# SparkFun_XBee_Serial_Explorer.net
KiCad netlist of a schematic drawn in EAGLE
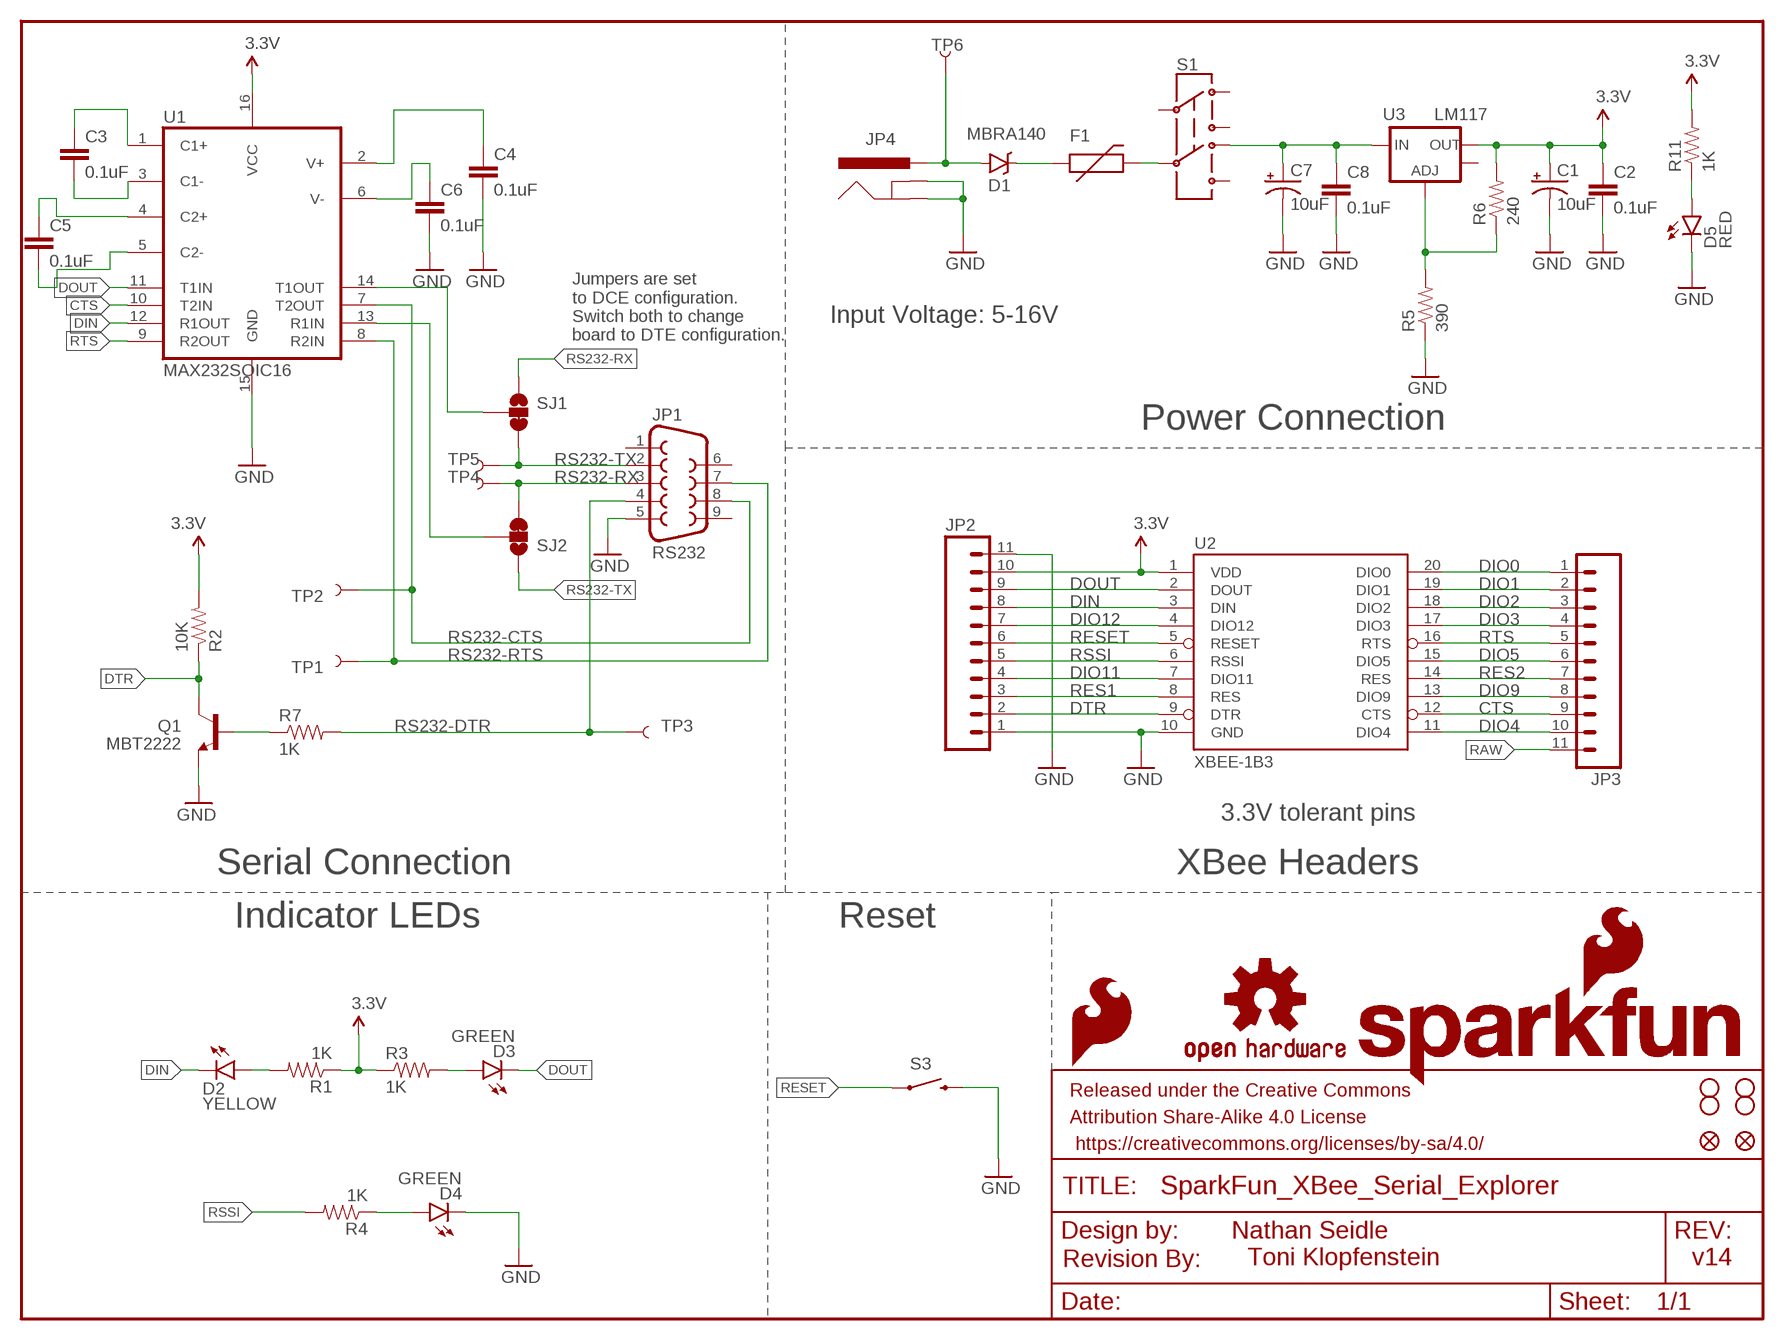
[diagram p0: schematic, sheet 1]

(export (version "E")
  (design (tool "Eeschema 10.0.6"))
  (components
    (comp (ref "C1")
      (value "10uF")
      (footprint "eagle-import:EIA3216")
      (libsource (lib "eagle-import") (part "10UF-16V-10%(TANT)"))
    )
    (comp (ref "C2")
      (value "0.1uF")
      (footprint "eagle-import:0603-CAP")
      (libsource (lib "eagle-import") (part "0.1UF-25V(+80/-20%)(0603)"))
    )
    (comp (ref "C3")
      (value "0.1uF")
      (footprint "eagle-import:0603-CAP")
      (libsource (lib "eagle-import") (part "0.1UF-25V(+80/-20%)(0603)"))
    )
    (comp (ref "C4")
      (value "0.1uF")
      (footprint "eagle-import:0603-CAP")
      (libsource (lib "eagle-import") (part "0.1UF-25V(+80/-20%)(0603)"))
    )
    (comp (ref "C5")
      (value "0.1uF")
      (footprint "eagle-import:0603-CAP")
      (libsource (lib "eagle-import") (part "0.1UF-25V(+80/-20%)(0603)"))
    )
    (comp (ref "C6")
      (value "0.1uF")
      (footprint "eagle-import:0603-CAP")
      (libsource (lib "eagle-import") (part "0.1UF-25V(+80/-20%)(0603)"))
    )
    (comp (ref "C7")
      (value "10uF")
      (footprint "eagle-import:EIA3216")
      (libsource (lib "eagle-import") (part "10UF-16V-10%(TANT)"))
    )
    (comp (ref "C8")
      (value "0.1uF")
      (footprint "eagle-import:0603-CAP")
      (libsource (lib "eagle-import") (part "0.1UF-25V(+80/-20%)(0603)"))
    )
    (comp (ref "D1")
      (value "MBRA140")
      (footprint "eagle-import:SMA-DIODE")
      (libsource (lib "eagle-import") (part "DIODE-SCHOTTKY-MBRA140"))
    )
    (comp (ref "D2")
      (value "YELLOW")
      (footprint "eagle-import:LED-1206")
      (libsource (lib "eagle-import") (part "LED-YELLOWLARGE"))
    )
    (comp (ref "D3")
      (value "GREEN")
      (footprint "eagle-import:LED-1206")
      (libsource (lib "eagle-import") (part "LED-GREENLARGE"))
    )
    (comp (ref "D4")
      (value "GREEN")
      (footprint "eagle-import:LED-1206")
      (libsource (lib "eagle-import") (part "LED-GREENLARGE"))
    )
    (comp (ref "D5")
      (value "RED")
      (footprint "eagle-import:LED-1206")
      (libsource (lib "eagle-import") (part "LED-RED1206"))
    )
    (comp (ref "F1")
      (value "PTCTHERMISTOR1206")
      (footprint "eagle-import:PTC-1206")
      (libsource (lib "eagle-import") (part "PTCTHERMISTOR1206"))
    )
    (comp (ref "FRAME1")
      (value "FRAME-LETTER")
      (footprint "eagle-import:CREATIVE_COMMONS")
      (libsource (lib "eagle-import") (part "FRAME-LETTER"))
    )
    (comp (ref "JP1")
      (value "RS232")
      (footprint "eagle-import:DB9")
      (libsource (lib "eagle-import") (part "DB9FEMALE"))
    )
    (comp (ref "JP2")
      (value "M11PTH")
      (footprint "eagle-import:1X11")
      (libsource (lib "eagle-import") (part "M11PTH"))
    )
    (comp (ref "JP3")
      (value "M11PTH")
      (footprint "eagle-import:1X11")
      (libsource (lib "eagle-import") (part "M11PTH"))
    )
    (comp (ref "JP4")
      (value "POWER_JACKPTH_LOCK")
      (footprint "eagle-import:POWER_JACK_PTH_LOCK")
      (libsource (lib "eagle-import") (part "POWER_JACKPTH_LOCK"))
    )
    (comp (ref "LOGO1")
      (value "OSHW-LOGOL")
      (footprint "eagle-import:OSHW-LOGO-L")
      (libsource (lib "eagle-import") (part "OSHW-LOGOL"))
    )
    (comp (ref "LOGO2")
      (value "SFE_LOGO_NAME_FLAME.2_INCH")
      (footprint "eagle-import:SFE_LOGO_NAME_FLAME_.2")
      (libsource (lib "eagle-import") (part "SFE_LOGO_NAME_FLAME.2_INCH"))
    )
    (comp (ref "LOGO3")
      (value "SFE_LOGO_FLAME.1_INCH")
      (footprint "eagle-import:SFE_LOGO_FLAME_.1")
      (libsource (lib "eagle-import") (part "SFE_LOGO_FLAME.1_INCH"))
    )
    (comp (ref "Q1")
      (value "MBT2222")
      (footprint "eagle-import:SOT23-3")
      (libsource (lib "eagle-import") (part "TRANSISTOR_NPNSOT23-3"))
    )
    (comp (ref "R1")
      (value "1K")
      (footprint "eagle-import:0603-RES")
      (libsource (lib "eagle-import") (part "1KOHM-1/10W-1%(0603)"))
    )
    (comp (ref "R2")
      (value "10K")
      (footprint "eagle-import:0603-RES")
      (libsource (lib "eagle-import") (part "10KOHM-1/10W-1%(0603)0603"))
    )
    (comp (ref "R3")
      (value "1K")
      (footprint "eagle-import:0603-RES")
      (libsource (lib "eagle-import") (part "1KOHM-1/10W-1%(0603)"))
    )
    (comp (ref "R4")
      (value "1K")
      (footprint "eagle-import:0603-RES")
      (libsource (lib "eagle-import") (part "1KOHM-1/10W-1%(0603)"))
    )
    (comp (ref "R5")
      (value "390")
      (footprint "eagle-import:0603-RES")
      (libsource (lib "eagle-import") (part "390OHM1/10W1%(0603)"))
    )
    (comp (ref "R6")
      (value "240")
      (footprint "eagle-import:0603-RES")
      (libsource (lib "eagle-import") (part "240OHM1/10W1%(0603)"))
    )
    (comp (ref "R7")
      (value "1K")
      (footprint "eagle-import:0603-RES")
      (libsource (lib "eagle-import") (part "1KOHM-1/10W-1%(0603)"))
    )
    (comp (ref "R11")
      (value "1K")
      (footprint "eagle-import:0603-RES")
      (libsource (lib "eagle-import") (part "1KOHM-1/10W-1%(0603)"))
    )
    (comp (ref "S1")
      (value "AYZ0202")
      (footprint "eagle-import:AYZ0202")
      (libsource (lib "eagle-import") (part "AYZ0202"))
    )
    (comp (ref "S3")
      (value "TAC_SWITCHSMD")
      (footprint "eagle-import:TACTILE-SWITCH-SMD")
      (libsource (lib "eagle-import") (part "SWITCH-MOMENTARY-2SMD-REDUNDANT"))
    )
    (comp (ref "SJ1")
      (value "JUMPER-PAD-3-2OF3_NC_BY_TRACE_SMALL")
      (footprint "eagle-import:PAD-JUMPER-3-2OF3_NC_BY_TRACE_YES_SILK_FULL_BOX")
      (libsource (lib "eagle-import") (part "JUMPER-PAD-3-2OF3_NC_BY_TRACE_SMALL"))
    )
    (comp (ref "SJ2")
      (value "JUMPER-PAD-3-2OF3_NC_BY_TRACE_SMALL")
      (footprint "eagle-import:PAD-JUMPER-3-2OF3_NC_BY_TRACE_YES_SILK_FULL_BOX")
      (libsource (lib "eagle-import") (part "JUMPER-PAD-3-2OF3_NC_BY_TRACE_SMALL"))
    )
    (comp (ref "TP1")
      (value "TEST-POINTTP_15TH_THRU")
      (footprint "eagle-import:TP_15TH")
      (libsource (lib "eagle-import") (part "TEST-POINTTP_15TH_THRU"))
    )
    (comp (ref "TP2")
      (value "TEST-POINTTP_15TH_THRU")
      (footprint "eagle-import:TP_15TH")
      (libsource (lib "eagle-import") (part "TEST-POINTTP_15TH_THRU"))
    )
    (comp (ref "TP3")
      (value "TEST-POINTTP_15TH_THRU")
      (footprint "eagle-import:TP_15TH")
      (libsource (lib "eagle-import") (part "TEST-POINTTP_15TH_THRU"))
    )
    (comp (ref "TP4")
      (value "TEST-POINTTP_15TH_THRU")
      (footprint "eagle-import:TP_15TH")
      (libsource (lib "eagle-import") (part "TEST-POINTTP_15TH_THRU"))
    )
    (comp (ref "TP5")
      (value "TEST-POINTTP_15TH_THRU")
      (footprint "eagle-import:TP_15TH")
      (libsource (lib "eagle-import") (part "TEST-POINTTP_15TH_THRU"))
    )
    (comp (ref "TP6")
      (value "TEST-POINTTP_15TH_THRU")
      (footprint "eagle-import:TP_15TH")
      (libsource (lib "eagle-import") (part "TEST-POINTTP_15TH_THRU"))
    )
    (comp (ref "U$1")
      (value "REVISION")
      (footprint "eagle-import:REVISION")
      (libsource (lib "eagle-import") (part "REVISION"))
    )
    (comp (ref "U$5")
      (value "STAND-OFF")
      (footprint "eagle-import:STAND-OFF")
      (libsource (lib "eagle-import") (part "STAND-OFF"))
    )
    (comp (ref "U$7")
      (value "FIDUCIAL1X2")
      (footprint "eagle-import:FIDUCIAL-1X2")
      (libsource (lib "eagle-import") (part "FIDUCIAL1X2"))
    )
    (comp (ref "U$9")
      (value "STAND-OFF")
      (footprint "eagle-import:STAND-OFF")
      (libsource (lib "eagle-import") (part "STAND-OFF"))
    )
    (comp (ref "U$10")
      (value "STAND-OFF")
      (footprint "eagle-import:STAND-OFF")
      (libsource (lib "eagle-import") (part "STAND-OFF"))
    )
    (comp (ref "U$11")
      (value "STAND-OFF")
      (footprint "eagle-import:STAND-OFF")
      (libsource (lib "eagle-import") (part "STAND-OFF"))
    )
    (comp (ref "U$16")
      (value "FIDUCIAL1X2")
      (footprint "eagle-import:FIDUCIAL-1X2")
      (libsource (lib "eagle-import") (part "FIDUCIAL1X2"))
    )
    (comp (ref "U1")
      (value "MAX232SOIC16")
      (footprint "eagle-import:SO016")
      (libsource (lib "eagle-import") (part "MAX232SOIC16"))
    )
    (comp (ref "U2")
      (value "XBEE-1B3")
      (footprint "eagle-import:XBEE-SMD")
      (libsource (lib "eagle-import") (part "XBEE-1B3"))
    )
    (comp (ref "U3")
      (value "LM117")
      (footprint "eagle-import:SOT223")
      (libsource (lib "eagle-import") (part "V_REG_LM1117SOT223"))
    )
  )
  (nets
    (net (code "1") (name "/DIO0") (class "Default")
      (node (ref "JP3") (pin "1") (pinfunction "1_1") (pintype "passive"))
      (node (ref "U2") (pin "20") (pinfunction "DIO0_20") (pintype "bidirectional"))
    )
    (net (code "2") (name "/DIO1") (class "Default")
      (node (ref "JP3") (pin "2") (pinfunction "2_2") (pintype "passive"))
      (node (ref "U2") (pin "19") (pinfunction "DIO1_19") (pintype "bidirectional"))
    )
    (net (code "3") (name "/DIO2") (class "Default")
      (node (ref "JP3") (pin "3") (pinfunction "3_3") (pintype "passive"))
      (node (ref "U2") (pin "18") (pinfunction "DIO2_18") (pintype "bidirectional"))
    )
    (net (code "4") (name "/DIO3") (class "Default")
      (node (ref "JP3") (pin "4") (pinfunction "4_4") (pintype "passive"))
      (node (ref "U2") (pin "17") (pinfunction "DIO3_17") (pintype "bidirectional"))
    )
    (net (code "5") (name "/DIO4") (class "Default")
      (node (ref "JP3") (pin "10") (pinfunction "10_10") (pintype "passive"))
      (node (ref "U2") (pin "11") (pinfunction "DIO4_11") (pintype "bidirectional"))
    )
    (net (code "6") (name "/DIO5") (class "Default")
      (node (ref "JP3") (pin "6") (pinfunction "6_6") (pintype "passive"))
      (node (ref "U2") (pin "15") (pinfunction "DIO5_15") (pintype "bidirectional"))
    )
    (net (code "7") (name "/DIO9") (class "Default")
      (node (ref "JP3") (pin "8") (pinfunction "8_8") (pintype "passive"))
      (node (ref "U2") (pin "13") (pinfunction "DIO9_13") (pintype "bidirectional"))
    )
    (net (code "8") (name "/DIO11") (class "Default")
      (node (ref "JP2") (pin "4") (pinfunction "4_4") (pintype "passive"))
      (node (ref "U2") (pin "7") (pinfunction "DIO11_7") (pintype "bidirectional"))
    )
    (net (code "9") (name "/DIO12") (class "Default")
      (node (ref "JP2") (pin "7") (pinfunction "7_7") (pintype "passive"))
      (node (ref "U2") (pin "4") (pinfunction "DIO12_4") (pintype "bidirectional"))
    )
    (net (code "10") (name "/RES1") (class "Default")
      (node (ref "JP2") (pin "3") (pinfunction "3_3") (pintype "passive"))
      (node (ref "U2") (pin "8") (pinfunction "RES_8") (pintype "bidirectional"))
    )
    (net (code "11") (name "/RES2") (class "Default")
      (node (ref "JP3") (pin "7") (pinfunction "7_7") (pintype "passive"))
      (node (ref "U2") (pin "14") (pinfunction "RES_14") (pintype "bidirectional"))
    )
    (net (code "12") (name "/RS232-CTS") (class "Default")
      (node (ref "JP1") (pin "8") (pinfunction "8_8") (pintype "passive"))
      (node (ref "TP2") (pin "P$1") (pinfunction "1_P$1") (pintype "bidirectional"))
      (node (ref "U1") (pin "7") (pinfunction "T2OUT_7") (pintype "output"))
    )
    (net (code "13") (name "/RS232-DTR") (class "Default")
      (node (ref "JP1") (pin "4") (pinfunction "4_4") (pintype "passive"))
      (node (ref "R7") (pin "2") (pinfunction "2_2") (pintype "passive"))
      (node (ref "TP3") (pin "P$1") (pinfunction "1_P$1") (pintype "bidirectional"))
    )
    (net (code "14") (name "/RS232-RTS") (class "Default")
      (node (ref "JP1") (pin "7") (pinfunction "7_7") (pintype "passive"))
      (node (ref "TP1") (pin "P$1") (pinfunction "1_P$1") (pintype "bidirectional"))
      (node (ref "U1") (pin "8") (pinfunction "R2IN_8") (pintype "input"))
    )
    (net (code "15") (name "3.3V") (class "Default")
      (node (ref "C1") (pin "A") (pinfunction "+_A") (pintype "passive"))
      (node (ref "C2") (pin "1") (pinfunction "1_1") (pintype "passive"))
      (node (ref "JP2") (pin "10") (pinfunction "10_10") (pintype "passive"))
      (node (ref "R1") (pin "1") (pinfunction "1_1") (pintype "passive"))
      (node (ref "R11") (pin "2") (pinfunction "2_2") (pintype "passive"))
      (node (ref "R2") (pin "2") (pinfunction "2_2") (pintype "passive"))
      (node (ref "R3") (pin "1") (pinfunction "1_1") (pintype "passive"))
      (node (ref "R6") (pin "2") (pinfunction "2_2") (pintype "passive"))
      (node (ref "U1") (pin "16") (pinfunction "VCC_16") (pintype "bidirectional"))
      (node (ref "U2") (pin "1") (pinfunction "VDD_1") (pintype "power_in"))
      (node (ref "U3") (pin "2") (pinfunction "OUT_2") (pintype "output"))
    )
    (net (code "16") (name "CTS") (class "Default")
      (node (ref "JP3") (pin "9") (pinfunction "9_9") (pintype "passive"))
      (node (ref "U1") (pin "10") (pinfunction "T2IN_10") (pintype "input"))
      (node (ref "U2") (pin "12") (pinfunction "CTS_12") (pintype "output"))
    )
    (net (code "17") (name "DIN") (class "Default")
      (node (ref "D2") (pin "C") (pinfunction "C_C") (pintype "passive"))
      (node (ref "JP2") (pin "8") (pinfunction "8_8") (pintype "passive"))
      (node (ref "U1") (pin "12") (pinfunction "R1OUT_12") (pintype "output"))
      (node (ref "U2") (pin "3") (pinfunction "DIN_3") (pintype "input"))
    )
    (net (code "18") (name "DOUT") (class "Default")
      (node (ref "D3") (pin "C") (pinfunction "C_C") (pintype "passive"))
      (node (ref "JP2") (pin "9") (pinfunction "9_9") (pintype "passive"))
      (node (ref "U1") (pin "11") (pinfunction "T1IN_11") (pintype "input"))
      (node (ref "U2") (pin "2") (pinfunction "DOUT_2") (pintype "output"))
    )
    (net (code "19") (name "DTR") (class "Default")
      (node (ref "JP2") (pin "2") (pinfunction "2_2") (pintype "passive"))
      (node (ref "Q1") (pin "3") (pinfunction "C_3") (pintype "passive"))
      (node (ref "R2") (pin "1") (pinfunction "1_1") (pintype "passive"))
      (node (ref "U2") (pin "9") (pinfunction "DTR_9") (pintype "bidirectional"))
    )
    (net (code "20") (name "GND") (class "Default")
      (node (ref "C1") (pin "C") (pinfunction "-_C") (pintype "passive"))
      (node (ref "C2") (pin "2") (pinfunction "2_2") (pintype "passive"))
      (node (ref "C4") (pin "2") (pinfunction "2_2") (pintype "passive"))
      (node (ref "C6") (pin "2") (pinfunction "2_2") (pintype "passive"))
      (node (ref "C7") (pin "C") (pinfunction "-_C") (pintype "passive"))
      (node (ref "C8") (pin "2") (pinfunction "2_2") (pintype "passive"))
      (node (ref "D4") (pin "C") (pinfunction "C_C") (pintype "passive"))
      (node (ref "D5") (pin "C") (pinfunction "C_C") (pintype "passive"))
      (node (ref "JP1") (pin "5") (pinfunction "5_5") (pintype "passive"))
      (node (ref "JP2") (pin "1") (pinfunction "1_1") (pintype "passive"))
      (node (ref "JP2") (pin "11") (pinfunction "11_11") (pintype "passive"))
      (node (ref "JP4") (pin "GND") (pinfunction "GND_GND") (pintype "bidirectional"))
      (node (ref "JP4") (pin "GNDBREAK") (pinfunction "GNDBREAK_GNDBREAK") (pintype "bidirectional"))
      (node (ref "Q1") (pin "2") (pinfunction "E_2") (pintype "passive"))
      (node (ref "R5") (pin "1") (pinfunction "1_1") (pintype "passive"))
      (node (ref "S3") (pin "3") (pinfunction "2_3") (pintype "passive"))
      (node (ref "S3") (pin "4") (pinfunction "2_4") (pintype "passive"))
      (node (ref "U1") (pin "15") (pinfunction "GND_15") (pintype "bidirectional"))
      (node (ref "U2") (pin "10") (pinfunction "GND_10") (pintype "power_in"))
    )
    (net (code "21") (name "Net-(D1-PadC)") (class "Default")
      (node (ref "D1") (pin "C") (pinfunction "C_C") (pintype "passive"))
      (node (ref "F1") (pin "1") (pinfunction "1_1") (pintype "bidirectional"))
    )
    (net (code "22") (name "Net-(D2-PadA)") (class "Default")
      (node (ref "D2") (pin "A") (pinfunction "A_A") (pintype "passive"))
      (node (ref "R1") (pin "2") (pinfunction "2_2") (pintype "passive"))
    )
    (net (code "23") (name "Net-(D3-PadA)") (class "Default")
      (node (ref "D3") (pin "A") (pinfunction "A_A") (pintype "passive"))
      (node (ref "R3") (pin "2") (pinfunction "2_2") (pintype "passive"))
    )
    (net (code "24") (name "Net-(D4-PadA)") (class "Default")
      (node (ref "D4") (pin "A") (pinfunction "A_A") (pintype "passive"))
      (node (ref "R4") (pin "1") (pinfunction "1_1") (pintype "passive"))
    )
    (net (code "25") (name "Net-(D5-PadA)") (class "Default")
      (node (ref "D5") (pin "A") (pinfunction "A_A") (pintype "passive"))
      (node (ref "R11") (pin "1") (pinfunction "1_1") (pintype "passive"))
    )
    (net (code "26") (name "Net-(F1-Pad2)") (class "Default")
      (node (ref "F1") (pin "2") (pinfunction "2_2") (pintype "bidirectional"))
      (node (ref "S1") (pin "5") (pinfunction "5_5") (pintype "bidirectional"))
    )
    (net (code "27") (name "Net-(Q1-B)") (class "Default")
      (node (ref "Q1") (pin "1") (pinfunction "B_1") (pintype "passive"))
      (node (ref "R7") (pin "1") (pinfunction "1_1") (pintype "passive"))
    )
    (net (code "28") (name "Net-(TP6-1)") (class "Default")
      (node (ref "D1") (pin "A") (pinfunction "A_A") (pintype "passive"))
      (node (ref "JP4") (pin "PWR") (pinfunction "PWR_PWR") (pintype "bidirectional"))
      (node (ref "TP6") (pin "P$1") (pinfunction "1_P$1") (pintype "bidirectional"))
    )
    (net (code "29") (name "Net-(U1-C1+)") (class "Default")
      (node (ref "C3") (pin "1") (pinfunction "1_1") (pintype "passive"))
      (node (ref "U1") (pin "1") (pinfunction "C1+_1") (pintype "bidirectional"))
    )
    (net (code "30") (name "Net-(U1-C1-)") (class "Default")
      (node (ref "C3") (pin "2") (pinfunction "2_2") (pintype "passive"))
      (node (ref "U1") (pin "3") (pinfunction "C1-_3") (pintype "bidirectional"))
    )
    (net (code "31") (name "Net-(U1-C2+)") (class "Default")
      (node (ref "C5") (pin "1") (pinfunction "1_1") (pintype "passive"))
      (node (ref "U1") (pin "4") (pinfunction "C2+_4") (pintype "bidirectional"))
    )
    (net (code "32") (name "Net-(U1-C2-)") (class "Default")
      (node (ref "C5") (pin "2") (pinfunction "2_2") (pintype "passive"))
      (node (ref "U1") (pin "5") (pinfunction "C2-_5") (pintype "bidirectional"))
    )
    (net (code "33") (name "Net-(U1-R1IN)") (class "Default")
      (node (ref "SJ2") (pin "2") (pinfunction "2_2") (pintype "passive"))
      (node (ref "U1") (pin "13") (pinfunction "R1IN_13") (pintype "input"))
    )
    (net (code "34") (name "Net-(U1-T1OUT)") (class "Default")
      (node (ref "SJ1") (pin "2") (pinfunction "2_2") (pintype "passive"))
      (node (ref "U1") (pin "14") (pinfunction "T1OUT_14") (pintype "output"))
    )
    (net (code "35") (name "Net-(U1-V+)") (class "Default")
      (node (ref "C4") (pin "1") (pinfunction "1_1") (pintype "passive"))
      (node (ref "U1") (pin "2") (pinfunction "V+_2") (pintype "bidirectional"))
    )
    (net (code "36") (name "Net-(U1-V-)") (class "Default")
      (node (ref "C6") (pin "1") (pinfunction "1_1") (pintype "passive"))
      (node (ref "U1") (pin "6") (pinfunction "V-_6") (pintype "bidirectional"))
    )
    (net (code "37") (name "Net-(U3-ADJ)") (class "Default")
      (node (ref "R5") (pin "2") (pinfunction "2_2") (pintype "passive"))
      (node (ref "R6") (pin "1") (pinfunction "1_1") (pintype "passive"))
      (node (ref "U3") (pin "1") (pinfunction "ADJ_1") (pintype "input"))
    )
    (net (code "38") (name "RAW") (class "Default")
      (node (ref "C7") (pin "A") (pinfunction "+_A") (pintype "passive"))
      (node (ref "C8") (pin "1") (pinfunction "1_1") (pintype "passive"))
      (node (ref "JP3") (pin "11") (pinfunction "11_11") (pintype "passive"))
      (node (ref "S1") (pin "6") (pinfunction "4_6") (pintype "bidirectional"))
      (node (ref "U3") (pin "3") (pinfunction "IN_3") (pintype "input"))
    )
    (net (code "39") (name "RESET") (class "Default")
      (node (ref "JP2") (pin "6") (pinfunction "6_6") (pintype "passive"))
      (node (ref "S3") (pin "1") (pinfunction "1_1") (pintype "passive"))
      (node (ref "S3") (pin "2") (pinfunction "1_2") (pintype "passive"))
      (node (ref "U2") (pin "5") (pinfunction "RESET_5") (pintype "input"))
    )
    (net (code "40") (name "RS232-RX") (class "Default")
      (node (ref "JP1") (pin "3") (pinfunction "3_3") (pintype "passive"))
      (node (ref "SJ1") (pin "1") (pinfunction "1_1") (pintype "passive"))
      (node (ref "SJ2") (pin "3") (pinfunction "3_3") (pintype "passive"))
      (node (ref "TP4") (pin "P$1") (pinfunction "1_P$1") (pintype "bidirectional"))
    )
    (net (code "41") (name "RS232-TX") (class "Default")
      (node (ref "JP1") (pin "2") (pinfunction "2_2") (pintype "passive"))
      (node (ref "SJ1") (pin "3") (pinfunction "3_3") (pintype "passive"))
      (node (ref "SJ2") (pin "1") (pinfunction "1_1") (pintype "passive"))
      (node (ref "TP5") (pin "P$1") (pinfunction "1_P$1") (pintype "bidirectional"))
    )
    (net (code "42") (name "RSSI") (class "Default")
      (node (ref "JP2") (pin "5") (pinfunction "5_5") (pintype "passive"))
      (node (ref "R4") (pin "2") (pinfunction "2_2") (pintype "passive"))
      (node (ref "U2") (pin "6") (pinfunction "RSSI_6") (pintype "bidirectional"))
    )
    (net (code "43") (name "RTS") (class "Default")
      (node (ref "JP3") (pin "5") (pinfunction "5_5") (pintype "passive"))
      (node (ref "U1") (pin "9") (pinfunction "R2OUT_9") (pintype "output"))
      (node (ref "U2") (pin "16") (pinfunction "RTS_16") (pintype "input"))
    )
    (net (code "44") (name "unconnected-(JP1-Pad1)") (class "Default")
      (node (ref "JP1") (pin "1") (pinfunction "1_1") (pintype "passive"))
    )
    (net (code "45") (name "unconnected-(JP1-Pad6)") (class "Default")
      (node (ref "JP1") (pin "6") (pinfunction "6_6") (pintype "passive"))
    )
    (net (code "46") (name "unconnected-(JP1-Pad9)") (class "Default")
      (node (ref "JP1") (pin "9") (pinfunction "9_9") (pintype "passive"))
    )
    (net (code "47") (name "unconnected-(S1-1-Pad3)") (class "Default")
      (node (ref "S1") (pin "3") (pinfunction "1_3") (pintype "bidirectional"))
    )
    (net (code "48") (name "unconnected-(S1-3-Pad1)") (class "Default")
      (node (ref "S1") (pin "1") (pinfunction "3_1") (pintype "bidirectional"))
    )
    (net (code "49") (name "unconnected-(S1-6-Pad4)") (class "Default")
      (node (ref "S1") (pin "4") (pinfunction "6_4") (pintype "bidirectional"))
    )
    (net (code "50") (name "unconnected-(S1-Pad2)") (class "Default")
      (node (ref "S1") (pin "2") (pinfunction "2_2") (pintype "bidirectional"))
    )
    (net (code "51") (name "unconnected-(U3-OUT-Pad4)") (class "Default")
      (node (ref "U3") (pin "4") (pinfunction "OUT_4") (pintype "output"))
    )
  )
)
